# AnalogEx_2RedLedFadeInFadeOutUSB.net
KiCad netlist of a schematic drawn in EAGLE
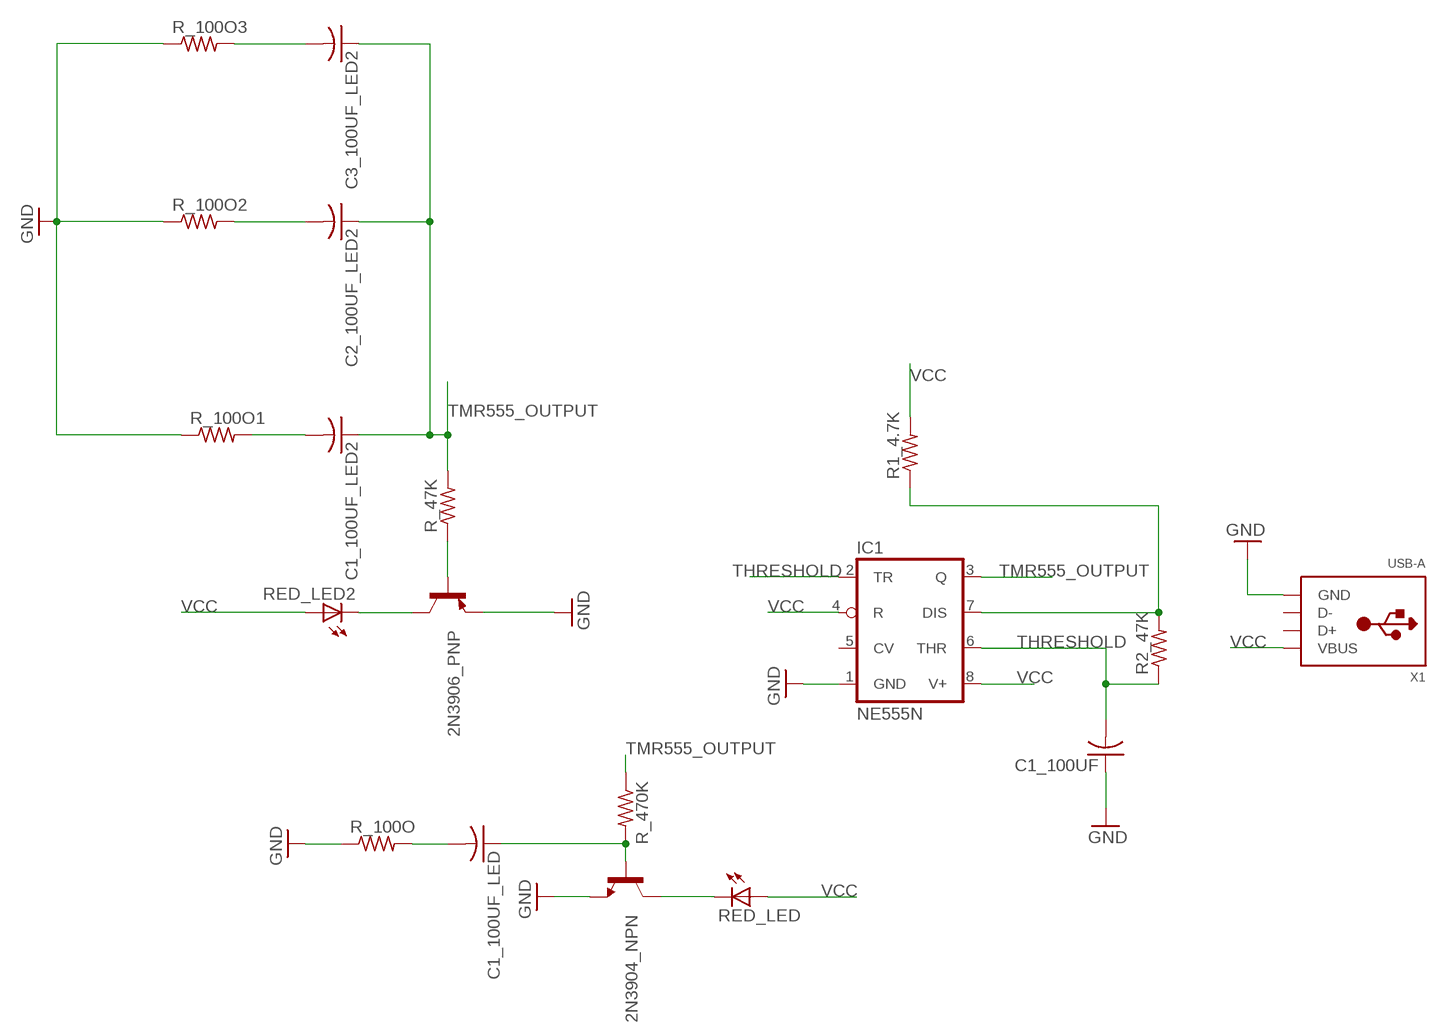
[diagram p0: schematic, sheet 1]

(export (version "E")
  (design (tool "Eeschema 10.0.6"))
  (components
    (comp (ref "2N3904_NPN")
      (value "MMBT3904LT1-NPN-SOT23-BEC")
      (footprint "eagle-import:SOT23-BEC")
      (libsource (lib "eagle-import") (part "-NPN-SOT23-BECMMBT3904LT1"))
    )
    (comp (ref "2N3906_PNP")
      (value "MMBT3906LT1SMD")
      (footprint "eagle-import:SOT23-BEC")
      (libsource (lib "eagle-import") (part "MMBT3906SMDLT1"))
    )
    (comp (ref "C1_100UF")
      (value "C-US025-030X050")
      (footprint "eagle-import:C025-030X050")
      (libsource (lib "eagle-import") (part "C-US025-030X050"))
    )
    (comp (ref "C1_100UF_LED")
      (value "C-US025-030X050")
      (footprint "eagle-import:C025-030X050")
      (libsource (lib "eagle-import") (part "C-US025-030X050"))
    )
    (comp (ref "C1_100UF_LED2")
      (value "C-US025-030X050")
      (footprint "eagle-import:C025-030X050")
      (libsource (lib "eagle-import") (part "C-US025-030X050"))
    )
    (comp (ref "C2_100UF_LED2")
      (value "C-US025-030X050")
      (footprint "eagle-import:C025-030X050")
      (libsource (lib "eagle-import") (part "C-US025-030X050"))
    )
    (comp (ref "C3_100UF_LED2")
      (value "C-US025-030X050")
      (footprint "eagle-import:C025-030X050")
      (libsource (lib "eagle-import") (part "C-US025-030X050"))
    )
    (comp (ref "IC1")
      (value "NE555N")
      (footprint "eagle-import:DIL08")
      (libsource (lib "eagle-import") (part "555NNE"))
    )
    (comp (ref "R1_4.7K")
      (value "R-US_R1206")
      (footprint "eagle-import:R1206")
      (libsource (lib "eagle-import") (part "R-US_R1206"))
    )
    (comp (ref "R2_47K")
      (value "R-US_R1206")
      (footprint "eagle-import:R1206")
      (libsource (lib "eagle-import") (part "R-US_R1206"))
    )
    (comp (ref "RED_LED")
      (value "LED5MM")
      (footprint "eagle-import:LED5MM")
      (libsource (lib "eagle-import") (part "LED5MM"))
    )
    (comp (ref "RED_LED2")
      (value "LED5MM")
      (footprint "eagle-import:LED5MM")
      (libsource (lib "eagle-import") (part "LED5MM"))
    )
    (comp (ref "R_47K")
      (value "R-US_R1206")
      (footprint "eagle-import:R1206")
      (libsource (lib "eagle-import") (part "R-US_R1206"))
    )
    (comp (ref "R_100O")
      (value "R-US_R1206")
      (footprint "eagle-import:R1206")
      (libsource (lib "eagle-import") (part "R-US_R1206"))
    )
    (comp (ref "R_100O1")
      (value "R-US_R1206")
      (footprint "eagle-import:R1206")
      (libsource (lib "eagle-import") (part "R-US_R1206"))
    )
    (comp (ref "R_100O2")
      (value "R-US_R1206")
      (footprint "eagle-import:R1206")
      (libsource (lib "eagle-import") (part "R-US_R1206"))
    )
    (comp (ref "R_100O3")
      (value "R-US_R1206")
      (footprint "eagle-import:R1206")
      (libsource (lib "eagle-import") (part "R-US_R1206"))
    )
    (comp (ref "R_470K")
      (value "R-US_R1206")
      (footprint "eagle-import:R1206")
      (libsource (lib "eagle-import") (part "R-US_R1206"))
    )
    (comp (ref "X1")
      (value "USB-A")
      (footprint "eagle-import:MOLEX_480371000")
      (libsource (lib "eagle-import") (part "USB-A"))
    )
  )
  (nets
    (net (code "1") (name "/THRESHOLD") (class "Default")
      (node (ref "C1_100UF") (pin "2") (pinfunction "2_2") (pintype "passive"))
      (node (ref "IC1") (pin "2") (pinfunction "TR_2") (pintype "input"))
      (node (ref "IC1") (pin "6") (pinfunction "THR_6") (pintype "input"))
      (node (ref "R2_47K") (pin "1") (pinfunction "1_1") (pintype "passive"))
    )
    (net (code "2") (name "/TMR555_OUTPUT") (class "Default")
      (node (ref "C1_100UF_LED2") (pin "1") (pinfunction "1_1") (pintype "passive"))
      (node (ref "C2_100UF_LED2") (pin "1") (pinfunction "1_1") (pintype "passive"))
      (node (ref "C3_100UF_LED2") (pin "1") (pinfunction "1_1") (pintype "passive"))
      (node (ref "IC1") (pin "3") (pinfunction "Q_3") (pintype "output"))
      (node (ref "R_470K") (pin "1") (pinfunction "1_1") (pintype "passive"))
      (node (ref "R_47K") (pin "2") (pinfunction "2_2") (pintype "passive"))
    )
    (net (code "3") (name "/VCC") (class "Default")
      (node (ref "IC1") (pin "4") (pinfunction "R_4") (pintype "input"))
      (node (ref "IC1") (pin "8") (pinfunction "V+_8") (pintype "power_in"))
      (node (ref "R1_4.7K") (pin "2") (pinfunction "2_2") (pintype "passive"))
      (node (ref "RED_LED") (pin "A") (pinfunction "A_A") (pintype "passive"))
      (node (ref "RED_LED2") (pin "A") (pinfunction "A_A") (pintype "passive"))
      (node (ref "X1") (pin "1") (pinfunction "VBUS_1") (pintype "power_in"))
    )
    (net (code "4") (name "GND") (class "Default")
      (node (ref "2N3904_NPN") (pin "E") (pinfunction "E_E") (pintype "passive"))
      (node (ref "2N3906_PNP") (pin "E") (pinfunction "E_E") (pintype "passive"))
      (node (ref "C1_100UF") (pin "1") (pinfunction "1_1") (pintype "passive"))
      (node (ref "IC1") (pin "1") (pinfunction "GND_1") (pintype "power_in"))
      (node (ref "R_100O") (pin "1") (pinfunction "1_1") (pintype "passive"))
      (node (ref "R_100O1") (pin "1") (pinfunction "1_1") (pintype "passive"))
      (node (ref "R_100O2") (pin "1") (pinfunction "1_1") (pintype "passive"))
      (node (ref "R_100O3") (pin "1") (pinfunction "1_1") (pintype "passive"))
      (node (ref "X1") (pin "4") (pinfunction "GND_4") (pintype "power_in"))
    )
    (net (code "5") (name "Net-(2N3904_NPN-PadB)") (class "Default")
      (node (ref "2N3904_NPN") (pin "B") (pinfunction "B_B") (pintype "passive"))
      (node (ref "C1_100UF_LED") (pin "1") (pinfunction "1_1") (pintype "passive"))
      (node (ref "R_470K") (pin "2") (pinfunction "2_2") (pintype "passive"))
    )
    (net (code "6") (name "Net-(2N3906_PNP-PadB)") (class "Default")
      (node (ref "2N3906_PNP") (pin "B") (pinfunction "B_B") (pintype "passive"))
      (node (ref "R_47K") (pin "1") (pinfunction "1_1") (pintype "passive"))
    )
    (net (code "7") (name "Net-(C1_100UF_LED-Pad2)") (class "Default")
      (node (ref "C1_100UF_LED") (pin "2") (pinfunction "2_2") (pintype "passive"))
      (node (ref "R_100O") (pin "2") (pinfunction "2_2") (pintype "passive"))
    )
    (net (code "8") (name "Net-(C1_100UF_LED2-Pad2)") (class "Default")
      (node (ref "C1_100UF_LED2") (pin "2") (pinfunction "2_2") (pintype "passive"))
      (node (ref "R_100O1") (pin "2") (pinfunction "2_2") (pintype "passive"))
    )
    (net (code "9") (name "Net-(C2_100UF_LED2-Pad2)") (class "Default")
      (node (ref "C2_100UF_LED2") (pin "2") (pinfunction "2_2") (pintype "passive"))
      (node (ref "R_100O2") (pin "2") (pinfunction "2_2") (pintype "passive"))
    )
    (net (code "10") (name "Net-(C3_100UF_LED2-Pad2)") (class "Default")
      (node (ref "C3_100UF_LED2") (pin "2") (pinfunction "2_2") (pintype "passive"))
      (node (ref "R_100O3") (pin "2") (pinfunction "2_2") (pintype "passive"))
    )
    (net (code "11") (name "Net-(IC1-DIS)") (class "Default")
      (node (ref "IC1") (pin "7") (pinfunction "DIS_7") (pintype "input"))
      (node (ref "R1_4.7K") (pin "1") (pinfunction "1_1") (pintype "passive"))
      (node (ref "R2_47K") (pin "2") (pinfunction "2_2") (pintype "passive"))
    )
    (net (code "12") (name "Net-(RED_LED-C)") (class "Default")
      (node (ref "2N3904_NPN") (pin "C") (pinfunction "C_C") (pintype "passive"))
      (node (ref "RED_LED") (pin "K") (pinfunction "C_K") (pintype "passive"))
    )
    (net (code "13") (name "Net-(RED_LED2-C)") (class "Default")
      (node (ref "2N3906_PNP") (pin "C") (pinfunction "C_C") (pintype "passive"))
      (node (ref "RED_LED2") (pin "K") (pinfunction "C_K") (pintype "passive"))
    )
    (net (code "14") (name "unconnected-(IC1-CV-Pad5)") (class "Default")
      (node (ref "IC1") (pin "5") (pinfunction "CV_5") (pintype "input"))
    )
    (net (code "15") (name "unconnected-(X1-D+-Pad3)") (class "Default")
      (node (ref "X1") (pin "3") (pinfunction "D+_3") (pintype "bidirectional"))
    )
    (net (code "16") (name "unconnected-(X1-D--Pad2)") (class "Default")
      (node (ref "X1") (pin "2") (pinfunction "D-_2") (pintype "bidirectional"))
    )
  )
)
